# LTC4150_BOB.net
KiCad netlist of a schematic drawn in EAGLE
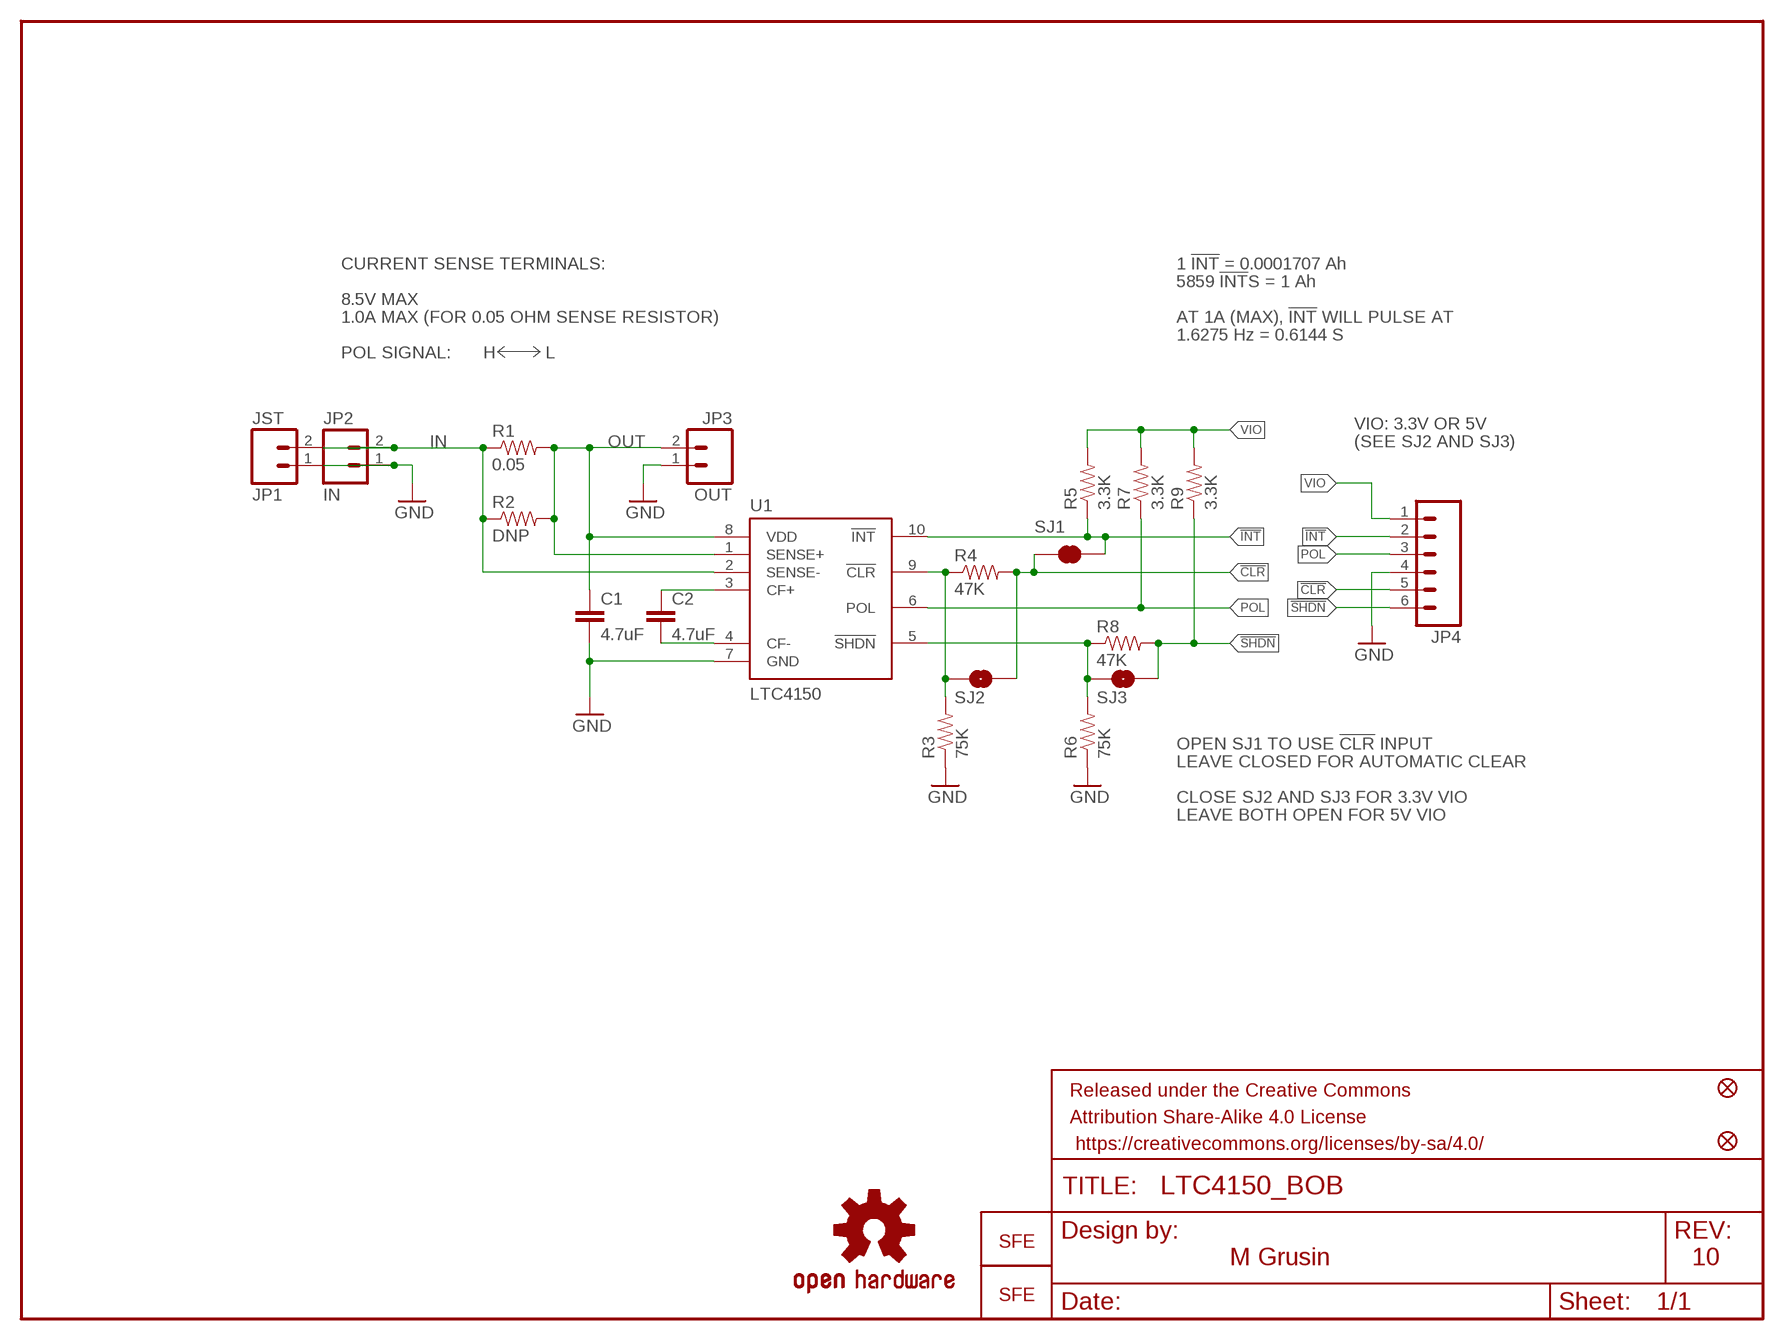
[diagram p0: schematic, sheet 1]

(export (version "E")
  (design (tool "Eeschema 10.0.6"))
  (components
    (comp (ref "C1")
      (value "4.7uF")
      (footprint "eagle-import:0603-CAP")
      (libsource (lib "eagle-import") (part "CAP0603-CAP"))
    )
    (comp (ref "C2")
      (value "4.7uF")
      (footprint "eagle-import:0603-CAP")
      (libsource (lib "eagle-import") (part "CAP0603-CAP"))
    )
    (comp (ref "FID1")
      (value "FIDUCIAL1X2")
      (footprint "eagle-import:FIDUCIAL-1X2")
      (libsource (lib "eagle-import") (part "FIDUCIAL1X2"))
    )
    (comp (ref "FID2")
      (value "FIDUCIAL1X2")
      (footprint "eagle-import:FIDUCIAL-1X2")
      (libsource (lib "eagle-import") (part "FIDUCIAL1X2"))
    )
    (comp (ref "FRAME1")
      (value "FRAME-LETTER")
      (footprint "eagle-import:CREATIVE_COMMONS")
      (libsource (lib "eagle-import") (part "FRAME-LETTER"))
    )
    (comp (ref "JP1")
      (value "JST")
      (footprint "eagle-import:JST-2-SMD")
      (libsource (lib "eagle-import") (part "M02-JST-2MM-SMT"))
    )
    (comp (ref "JP2")
      (value "IN")
      (footprint "eagle-import:1X02")
      (libsource (lib "eagle-import") (part "M02PTH"))
    )
    (comp (ref "JP3")
      (value "OUT")
      (footprint "eagle-import:1X02")
      (libsource (lib "eagle-import") (part "M02PTH"))
    )
    (comp (ref "JP4")
      (value "M06SIP")
      (footprint "eagle-import:1X06")
      (libsource (lib "eagle-import") (part "M06SIP"))
    )
    (comp (ref "LOGO1")
      (value "OSHW-LOGOS")
      (footprint "eagle-import:OSHW-LOGO-S")
      (libsource (lib "eagle-import") (part "OSHW-LOGOS"))
    )
    (comp (ref "LOGO2")
      (value "LOGO-SFENW2")
      (footprint "eagle-import:SFE-NEW-WEB")
      (libsource (lib "eagle-import") (part "LOGO-SFENW2"))
    )
    (comp (ref "LOGO3")
      (value "LOGO-SFESK")
      (footprint "eagle-import:SFE-LOGO-FLAME")
      (libsource (lib "eagle-import") (part "LOGO-SFESK"))
    )
    (comp (ref "R1")
      (value "0.05")
      (footprint "eagle-import:1206")
      (libsource (lib "eagle-import") (part "RESISTOR1206"))
    )
    (comp (ref "R2")
      (value "DNP")
      (footprint "eagle-import:AXIAL-0.3")
      (libsource (lib "eagle-import") (part "RESISTORAXIAL-0.3"))
    )
    (comp (ref "R3")
      (value "75K")
      (footprint "eagle-import:0603-RES")
      (libsource (lib "eagle-import") (part "RESISTOR0603-RES"))
    )
    (comp (ref "R4")
      (value "47K")
      (footprint "eagle-import:0603-RES")
      (libsource (lib "eagle-import") (part "RESISTOR0603-RES"))
    )
    (comp (ref "R5")
      (value "3.3K")
      (footprint "eagle-import:0603-RES")
      (libsource (lib "eagle-import") (part "RESISTOR0603-RES"))
    )
    (comp (ref "R6")
      (value "75K")
      (footprint "eagle-import:0603-RES")
      (libsource (lib "eagle-import") (part "RESISTOR0603-RES"))
    )
    (comp (ref "R7")
      (value "3.3K")
      (footprint "eagle-import:0603-RES")
      (libsource (lib "eagle-import") (part "RESISTOR0603-RES"))
    )
    (comp (ref "R8")
      (value "47K")
      (footprint "eagle-import:0603-RES")
      (libsource (lib "eagle-import") (part "RESISTOR0603-RES"))
    )
    (comp (ref "R9")
      (value "3.3K")
      (footprint "eagle-import:0603-RES")
      (libsource (lib "eagle-import") (part "RESISTOR0603-RES"))
    )
    (comp (ref "SJ1")
      (value "SOLDERJUMPERNC")
      (footprint "eagle-import:SJ_2S")
      (libsource (lib "eagle-import") (part "SOLDERJUMPERNC"))
    )
    (comp (ref "SJ2")
      (value "SOLDERJUMPERNO")
      (footprint "eagle-import:SJ_2S-NO")
      (libsource (lib "eagle-import") (part "SOLDERJUMPERNO"))
    )
    (comp (ref "SJ3")
      (value "SOLDERJUMPERNO")
      (footprint "eagle-import:SJ_2S-NO")
      (libsource (lib "eagle-import") (part "SOLDERJUMPERNO"))
    )
    (comp (ref "U1")
      (value "LTC4150")
      (footprint "eagle-import:MSOP10")
      (libsource (lib "eagle-import") (part "LTC4150"))
    )
  )
  (nets
    (net (code "1") (name "/IN") (class "Default")
      (node (ref "JP1") (pin "2") (pinfunction "1_2") (pintype "passive"))
      (node (ref "JP2") (pin "2") (pinfunction "2_2") (pintype "passive"))
      (node (ref "R1") (pin "1") (pinfunction "1_1") (pintype "passive"))
      (node (ref "R2") (pin "P$1") (pinfunction "1_P$1") (pintype "passive"))
      (node (ref "U1") (pin "2") (pinfunction "SENSE-_2") (pintype "bidirectional"))
    )
    (net (code "2") (name "/OUT") (class "Default")
      (node (ref "C1") (pin "1") (pinfunction "1_1") (pintype "passive"))
      (node (ref "JP3") (pin "2") (pinfunction "2_2") (pintype "passive"))
      (node (ref "R1") (pin "2") (pinfunction "2_2") (pintype "passive"))
      (node (ref "R2") (pin "P$2") (pinfunction "2_P$2") (pintype "passive"))
      (node (ref "U1") (pin "1") (pinfunction "SENSE+_1") (pintype "bidirectional"))
      (node (ref "U1") (pin "8") (pinfunction "VDD_8") (pintype "power_in"))
    )
    (net (code "3") (name "/~{CLR}") (class "Default")
      (node (ref "JP4") (pin "5") (pinfunction "5_5") (pintype "passive"))
      (node (ref "R4") (pin "2") (pinfunction "2_2") (pintype "passive"))
      (node (ref "SJ1") (pin "1") (pinfunction "1_1") (pintype "passive"))
      (node (ref "SJ2") (pin "2") (pinfunction "2_2") (pintype "passive"))
    )
    (net (code "4") (name "/~{INT}") (class "Default")
      (node (ref "JP4") (pin "2") (pinfunction "2_2") (pintype "passive"))
      (node (ref "R5") (pin "1") (pinfunction "1_1") (pintype "passive"))
      (node (ref "SJ1") (pin "2") (pinfunction "2_2") (pintype "passive"))
      (node (ref "U1") (pin "10") (pinfunction "~{INT}_10") (pintype "bidirectional"))
    )
    (net (code "5") (name "/~{SHDN}") (class "Default")
      (node (ref "JP4") (pin "6") (pinfunction "6_6") (pintype "passive"))
      (node (ref "R8") (pin "2") (pinfunction "2_2") (pintype "passive"))
      (node (ref "R9") (pin "1") (pinfunction "1_1") (pintype "passive"))
      (node (ref "SJ3") (pin "2") (pinfunction "2_2") (pintype "passive"))
    )
    (net (code "6") (name "GND") (class "Default")
      (node (ref "C1") (pin "2") (pinfunction "2_2") (pintype "passive"))
      (node (ref "JP1") (pin "1") (pinfunction "2_1") (pintype "passive"))
      (node (ref "JP2") (pin "1") (pinfunction "1_1") (pintype "passive"))
      (node (ref "JP3") (pin "1") (pinfunction "1_1") (pintype "passive"))
      (node (ref "JP4") (pin "4") (pinfunction "4_4") (pintype "passive"))
      (node (ref "R3") (pin "1") (pinfunction "1_1") (pintype "passive"))
      (node (ref "R6") (pin "1") (pinfunction "1_1") (pintype "passive"))
      (node (ref "U1") (pin "7") (pinfunction "GND_7") (pintype "power_in"))
    )
    (net (code "7") (name "Net-(U1-CF+)") (class "Default")
      (node (ref "C2") (pin "1") (pinfunction "1_1") (pintype "passive"))
      (node (ref "U1") (pin "3") (pinfunction "CF+_3") (pintype "bidirectional"))
    )
    (net (code "8") (name "Net-(U1-CF-)") (class "Default")
      (node (ref "C2") (pin "2") (pinfunction "2_2") (pintype "passive"))
      (node (ref "U1") (pin "4") (pinfunction "CF-_4") (pintype "bidirectional"))
    )
    (net (code "9") (name "Net-(U1-~{CLR})") (class "Default")
      (node (ref "R3") (pin "2") (pinfunction "2_2") (pintype "passive"))
      (node (ref "R4") (pin "1") (pinfunction "1_1") (pintype "passive"))
      (node (ref "SJ2") (pin "1") (pinfunction "1_1") (pintype "passive"))
      (node (ref "U1") (pin "9") (pinfunction "~{CLR}_9") (pintype "bidirectional"))
    )
    (net (code "10") (name "Net-(U1-~{SHDN})") (class "Default")
      (node (ref "R6") (pin "2") (pinfunction "2_2") (pintype "passive"))
      (node (ref "R8") (pin "1") (pinfunction "1_1") (pintype "passive"))
      (node (ref "SJ3") (pin "1") (pinfunction "1_1") (pintype "passive"))
      (node (ref "U1") (pin "5") (pinfunction "~{SHDN}_5") (pintype "input"))
    )
    (net (code "11") (name "POL") (class "Default")
      (node (ref "JP4") (pin "3") (pinfunction "3_3") (pintype "passive"))
      (node (ref "R7") (pin "1") (pinfunction "1_1") (pintype "passive"))
      (node (ref "U1") (pin "6") (pinfunction "POL_6") (pintype "bidirectional"))
    )
    (net (code "12") (name "VIO") (class "Default")
      (node (ref "JP4") (pin "1") (pinfunction "1_1") (pintype "passive"))
      (node (ref "R5") (pin "2") (pinfunction "2_2") (pintype "passive"))
      (node (ref "R7") (pin "2") (pinfunction "2_2") (pintype "passive"))
      (node (ref "R9") (pin "2") (pinfunction "2_2") (pintype "passive"))
    )
  )
)
